# FPGA_BANKS.net
KiCad netlist of a schematic drawn in Altium Designer
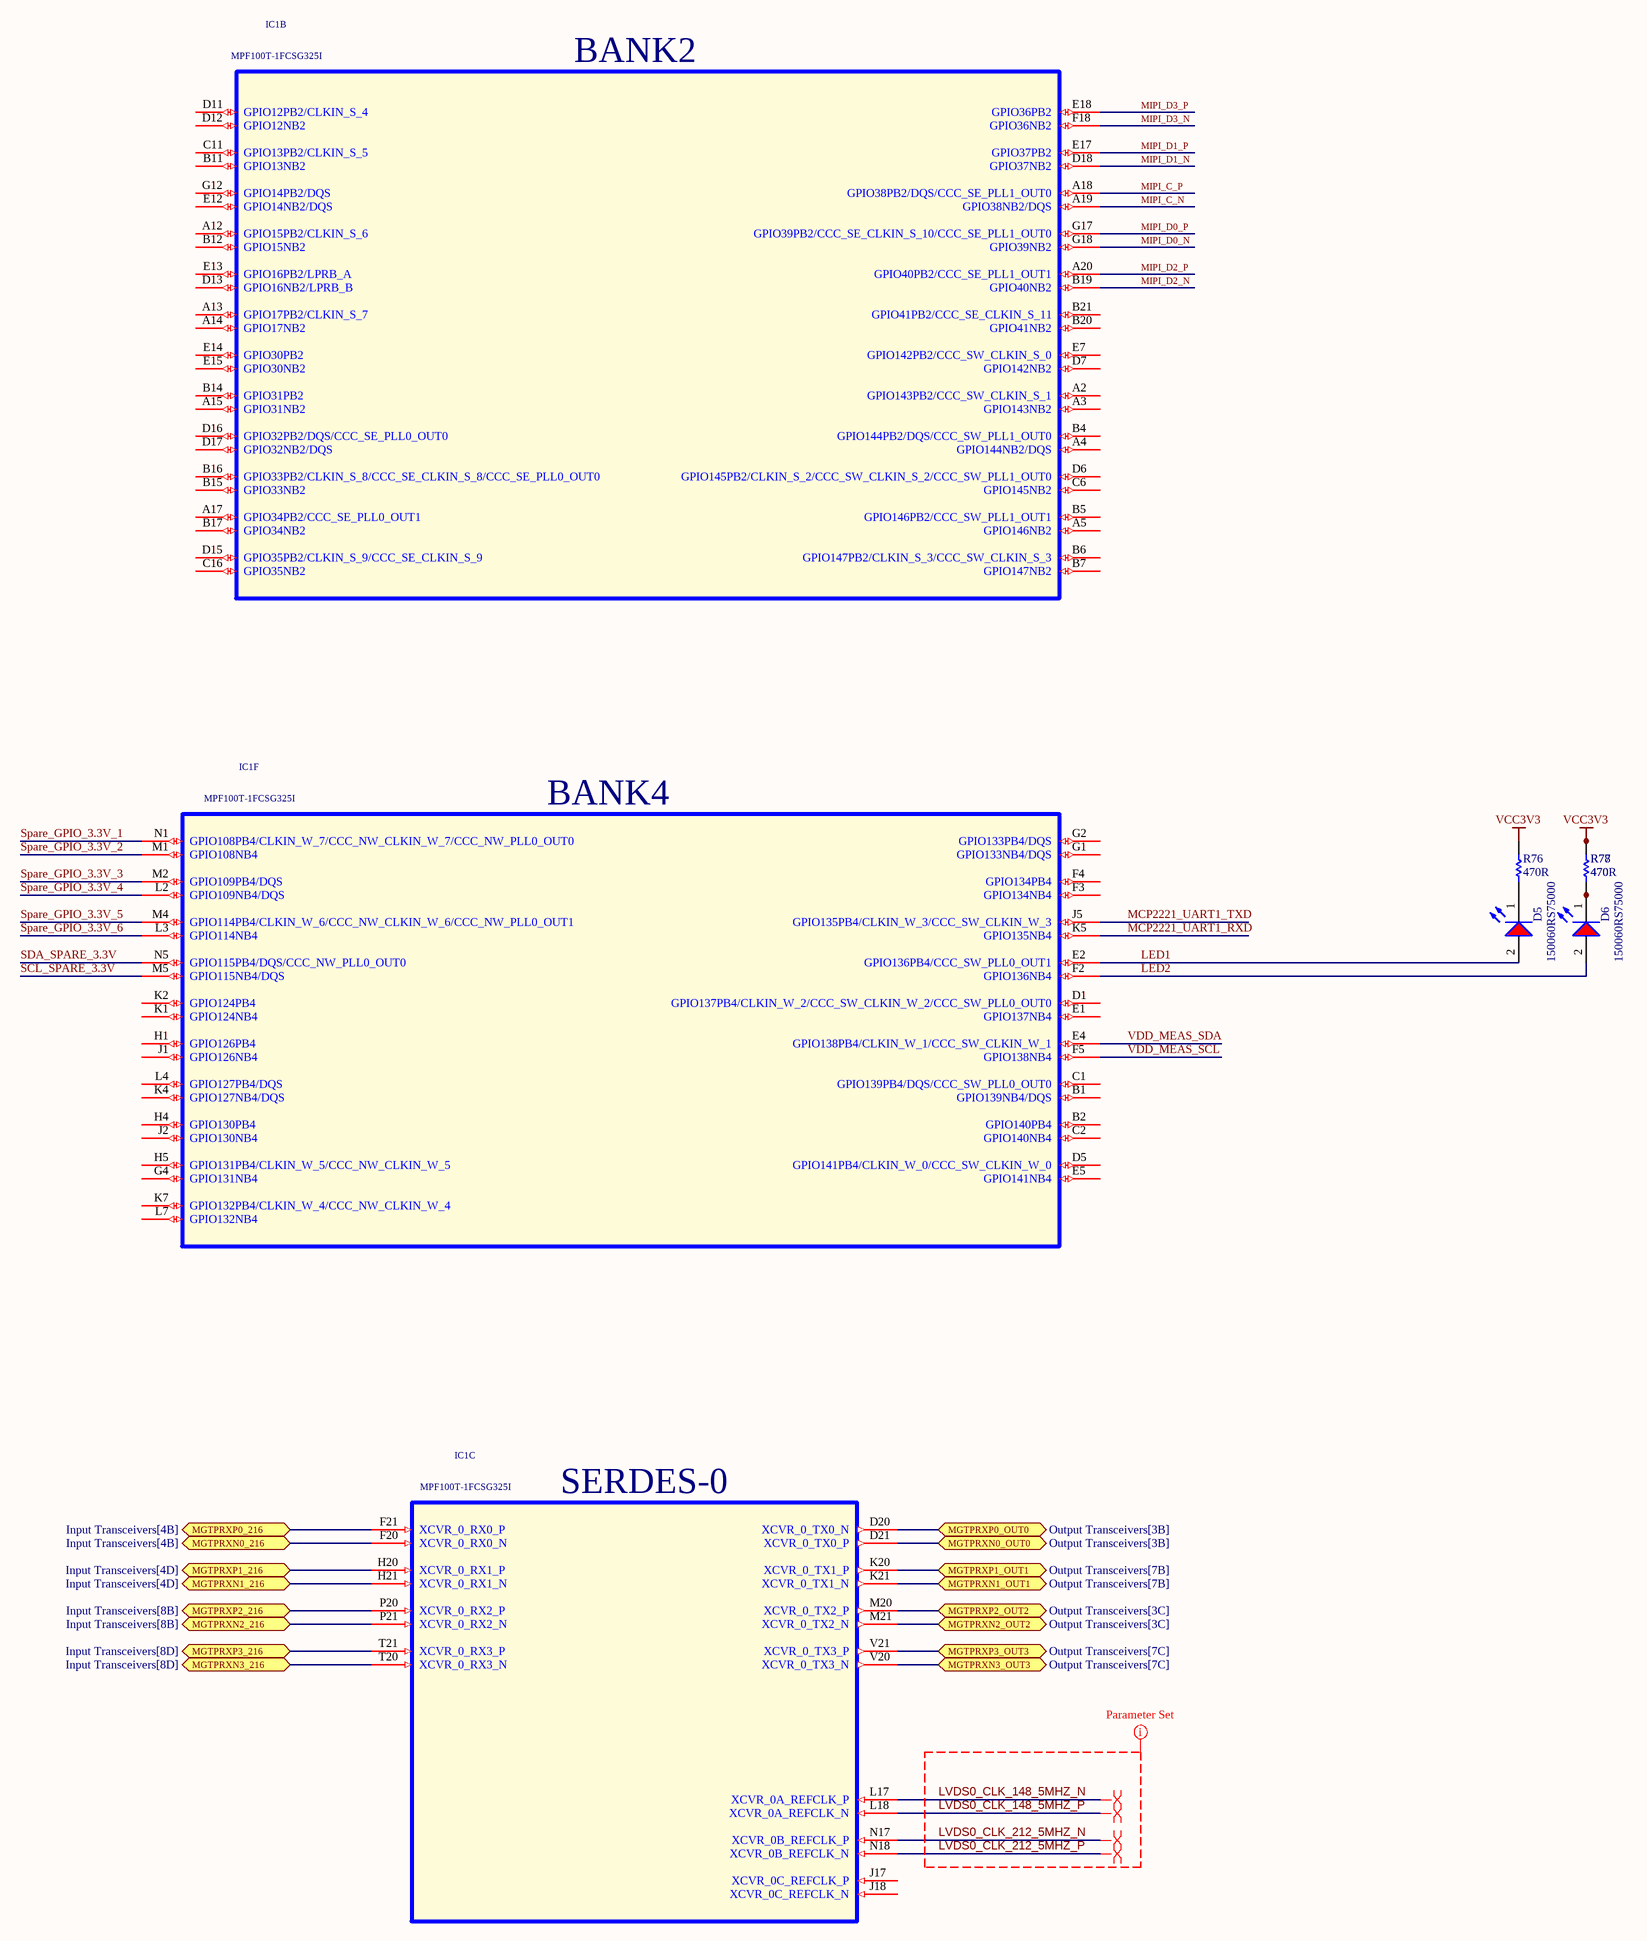
[diagram p0: FPGA_BANKS.SchDoc]

(export (version "E")
  (design (tool "Eeschema 10.0.6"))
  (components
    (comp (ref "D5")
      (value "150060RS75000")
      (footprint "WL-SMCW_0603_150060xx75000")
      (description "LED Low-Power Uni-Color Red 630nm 2V 2-Pin Chip 0603(1608Metric) T/R")
      (libsource (lib "Altium Content Vault") (part "LED_Red_2A-1K"))
    )
    (comp (ref "D6")
      (value "150060RS75000")
      (footprint "WL-SMCW_0603_150060xx75000")
      (description "LED Low-Power Uni-Color Red 630nm 2V 2-Pin Chip 0603(1608Metric) T/R")
      (libsource (lib "Altium Content Vault") (part "LED_Red_2A-1K"))
    )
    (comp (ref "IC1")
      (value "MPF100T-1FCSG325I")
      (footprint "PCB_Display_Doru:MPF100T-1FCSG325I")
      (fields (field (name "PART_NUMBER") "J00001"))
      (libsource (lib "PCB_Display_Doru") (part "MPF100T-1FCSG325I"))
    )
    (comp (ref "R76")
      (value "470R")
      (footprint "RESC1005X40X25ML05T10")
      (fields (field (name "PART NUMBER") "RC0402FR-07470RL") (field (name "MANUFACTURER") "Yageo / Phycomp"))
      (libsource (lib "Altium Content Vault") (part "RES"))
    )
    (comp (ref "R77")
      (value "470")
      (footprint "RESC1005X40X25ML05T10")
      (fields (field (name "PART NUMBER") "RC0402FR-07470RL") (field (name "MANUFACTURER") "Yageo / Phycomp"))
      (libsource (lib "Altium Content Vault") (part "RES"))
    )
    (comp (ref "R78")
      (value "470R")
      (footprint "RESC1005X40X25ML05T10")
      (fields (field (name "PART NUMBER") "RC0402FR-07470RL") (field (name "MANUFACTURER") "Yageo / Phycomp"))
      (libsource (lib "Altium Content Vault") (part "RES"))
    )
  )
  (nets
    (net (code "1") (name "/LED1") (class "Default")
      (node (ref "D5") (pin "2") (pinfunction "A_2") (pintype "passive"))
      (node (ref "IC1") (pin "E2") (pinfunction "GPIO136PB4/CCC_SW_PLL0_OUT1_E2") (pintype "bidirectional"))
    )
    (net (code "2") (name "/LED2") (class "Default")
      (node (ref "D6") (pin "2") (pinfunction "A_2") (pintype "passive"))
      (node (ref "IC1") (pin "F2") (pinfunction "GPIO136NB4_F2") (pintype "bidirectional"))
    )
    (net (code "3") (name "/LVDS0_CLK_148_5MHZ_N") (class "Default")
      (node (ref "IC1") (pin "L17") (pinfunction "XCVR_0A_REFCLK_P_L17") (pintype "input"))
    )
    (net (code "4") (name "/LVDS0_CLK_148_5MHZ_P") (class "Default")
      (node (ref "IC1") (pin "L18") (pinfunction "XCVR_0A_REFCLK_N_L18") (pintype "input"))
    )
    (net (code "5") (name "/LVDS0_CLK_212_5MHZ_N") (class "Default")
      (node (ref "IC1") (pin "N17") (pinfunction "XCVR_0B_REFCLK_P_N17") (pintype "input"))
    )
    (net (code "6") (name "/LVDS0_CLK_212_5MHZ_P") (class "Default")
      (node (ref "IC1") (pin "N18") (pinfunction "XCVR_0B_REFCLK_N_N18") (pintype "input"))
    )
    (net (code "7") (name "/MCP2221_UART1_RXD") (class "Default")
      (node (ref "IC1") (pin "K5") (pinfunction "GPIO135NB4_K5") (pintype "bidirectional"))
    )
    (net (code "8") (name "/MCP2221_UART1_TXD") (class "Default")
      (node (ref "IC1") (pin "J5") (pinfunction "GPIO135PB4/CLKIN_W_3/CCC_SW_CLKIN_W_3_J5") (pintype "bidirectional"))
    )
    (net (code "9") (name "/MGTPRXN0_216") (class "Default")
      (node (ref "IC1") (pin "F20") (pinfunction "XCVR_0_RX0_N_F20") (pintype "input"))
    )
    (net (code "10") (name "/MGTPRXN0_OUT0") (class "Default")
      (node (ref "IC1") (pin "D21") (pinfunction "XCVR_0_TX0_P_D21") (pintype "output"))
    )
    (net (code "11") (name "/MGTPRXN1_216") (class "Default")
      (node (ref "IC1") (pin "H21") (pinfunction "XCVR_0_RX1_N_H21") (pintype "input"))
    )
    (net (code "12") (name "/MGTPRXN1_OUT1") (class "Default")
      (node (ref "IC1") (pin "K21") (pinfunction "XCVR_0_TX1_N_K21") (pintype "output"))
    )
    (net (code "13") (name "/MGTPRXN2_216") (class "Default")
      (node (ref "IC1") (pin "P21") (pinfunction "XCVR_0_RX2_N_P21") (pintype "input"))
    )
    (net (code "14") (name "/MGTPRXN2_OUT2") (class "Default")
      (node (ref "IC1") (pin "M21") (pinfunction "XCVR_0_TX2_N_M21") (pintype "output"))
    )
    (net (code "15") (name "/MGTPRXN3_216") (class "Default")
      (node (ref "IC1") (pin "T20") (pinfunction "XCVR_0_RX3_N_T20") (pintype "input"))
    )
    (net (code "16") (name "/MGTPRXN3_OUT3") (class "Default")
      (node (ref "IC1") (pin "V20") (pinfunction "XCVR_0_TX3_N_V20") (pintype "output"))
    )
    (net (code "17") (name "/MGTPRXP0_216") (class "Default")
      (node (ref "IC1") (pin "F21") (pinfunction "XCVR_0_RX0_P_F21") (pintype "input"))
    )
    (net (code "18") (name "/MGTPRXP0_OUT0") (class "Default")
      (node (ref "IC1") (pin "D20") (pinfunction "XCVR_0_TX0_N_D20") (pintype "output"))
    )
    (net (code "19") (name "/MGTPRXP1_216") (class "Default")
      (node (ref "IC1") (pin "H20") (pinfunction "XCVR_0_RX1_P_H20") (pintype "input"))
    )
    (net (code "20") (name "/MGTPRXP1_OUT1") (class "Default")
      (node (ref "IC1") (pin "K20") (pinfunction "XCVR_0_TX1_P_K20") (pintype "output"))
    )
    (net (code "21") (name "/MGTPRXP2_216") (class "Default")
      (node (ref "IC1") (pin "P20") (pinfunction "XCVR_0_RX2_P_P20") (pintype "input"))
    )
    (net (code "22") (name "/MGTPRXP2_OUT2") (class "Default")
      (node (ref "IC1") (pin "M20") (pinfunction "XCVR_0_TX2_P_M20") (pintype "output"))
    )
    (net (code "23") (name "/MGTPRXP3_216") (class "Default")
      (node (ref "IC1") (pin "T21") (pinfunction "XCVR_0_RX3_P_T21") (pintype "input"))
    )
    (net (code "24") (name "/MGTPRXP3_OUT3") (class "Default")
      (node (ref "IC1") (pin "V21") (pinfunction "XCVR_0_TX3_P_V21") (pintype "output"))
    )
    (net (code "25") (name "/MIPI_C_N") (class "Default")
      (node (ref "IC1") (pin "A19") (pinfunction "GPIO38NB2/DQS_A19") (pintype "bidirectional"))
    )
    (net (code "26") (name "/MIPI_C_P") (class "Default")
      (node (ref "IC1") (pin "A18") (pinfunction "GPIO38PB2/DQS/CCC_SE_PLL1_OUT0_A18") (pintype "bidirectional"))
    )
    (net (code "27") (name "/MIPI_D0_N") (class "Default")
      (node (ref "IC1") (pin "G18") (pinfunction "GPIO39NB2_G18") (pintype "bidirectional"))
    )
    (net (code "28") (name "/MIPI_D0_P") (class "Default")
      (node (ref "IC1") (pin "G17") (pinfunction "GPIO39PB2/CCC_SE_CLKIN_S_10/CCC_SE_PLL1_OUT0_G17") (pintype "bidirectional"))
    )
    (net (code "29") (name "/MIPI_D1_N") (class "Default")
      (node (ref "IC1") (pin "D18") (pinfunction "GPIO37NB2_D18") (pintype "bidirectional"))
    )
    (net (code "30") (name "/MIPI_D1_P") (class "Default")
      (node (ref "IC1") (pin "E17") (pinfunction "GPIO37PB2_E17") (pintype "bidirectional"))
    )
    (net (code "31") (name "/MIPI_D2_N") (class "Default")
      (node (ref "IC1") (pin "B19") (pinfunction "GPIO40NB2_B19") (pintype "bidirectional"))
    )
    (net (code "32") (name "/MIPI_D2_P") (class "Default")
      (node (ref "IC1") (pin "A20") (pinfunction "GPIO40PB2/CCC_SE_PLL1_OUT1_A20") (pintype "bidirectional"))
    )
    (net (code "33") (name "/MIPI_D3_N") (class "Default")
      (node (ref "IC1") (pin "F18") (pinfunction "GPIO36NB2_F18") (pintype "bidirectional"))
    )
    (net (code "34") (name "/MIPI_D3_P") (class "Default")
      (node (ref "IC1") (pin "E18") (pinfunction "GPIO36PB2_E18") (pintype "bidirectional"))
    )
    (net (code "35") (name "/SCL_SPARE_3.3V") (class "Default")
      (node (ref "IC1") (pin "M5") (pinfunction "GPIO115NB4/DQS_M5") (pintype "bidirectional"))
    )
    (net (code "36") (name "/SDA_SPARE_3.3V") (class "Default")
      (node (ref "IC1") (pin "N5") (pinfunction "GPIO115PB4/DQS/CCC_NW_PLL0_OUT0_N5") (pintype "bidirectional"))
    )
    (net (code "37") (name "/Spare_GPIO_3.3V_1") (class "Default")
      (node (ref "IC1") (pin "N1") (pinfunction "GPIO108PB4/CLKIN_W_7/CCC_NW_CLKIN_W_7/CCC_NW_PLL0_OUT0_N1") (pintype "bidirectional"))
    )
    (net (code "38") (name "/Spare_GPIO_3.3V_2") (class "Default")
      (node (ref "IC1") (pin "M1") (pinfunction "GPIO108NB4_M1") (pintype "bidirectional"))
    )
    (net (code "39") (name "/Spare_GPIO_3.3V_3") (class "Default")
      (node (ref "IC1") (pin "M2") (pinfunction "GPIO109PB4/DQS_M2") (pintype "bidirectional"))
    )
    (net (code "40") (name "/Spare_GPIO_3.3V_4") (class "Default")
      (node (ref "IC1") (pin "L2") (pinfunction "GPIO109NB4/DQS_L2") (pintype "bidirectional"))
    )
    (net (code "41") (name "/Spare_GPIO_3.3V_5") (class "Default")
      (node (ref "IC1") (pin "M4") (pinfunction "GPIO114PB4/CLKIN_W_6/CCC_NW_CLKIN_W_6/CCC_NW_PLL0_OUT1_M4") (pintype "bidirectional"))
    )
    (net (code "42") (name "/Spare_GPIO_3.3V_6") (class "Default")
      (node (ref "IC1") (pin "L3") (pinfunction "GPIO114NB4_L3") (pintype "bidirectional"))
    )
    (net (code "43") (name "/VDD_MEAS_SCL") (class "Default")
      (node (ref "IC1") (pin "F5") (pinfunction "GPIO138NB4_F5") (pintype "bidirectional"))
    )
    (net (code "44") (name "/VDD_MEAS_SDA") (class "Default")
      (node (ref "IC1") (pin "E4") (pinfunction "GPIO138PB4/CLKIN_W_1/CCC_SW_CLKIN_W_1_E4") (pintype "bidirectional"))
    )
    (net (code "45") (name "Net-(D5-K)") (class "Default")
      (node (ref "D5") (pin "1") (pinfunction "K_1") (pintype "passive"))
      (node (ref "R76") (pin "1") (pinfunction "1_1") (pintype "passive"))
    )
    (net (code "46") (name "Net-(D6-K)") (class "Default")
      (node (ref "D6") (pin "1") (pinfunction "K_1") (pintype "passive"))
      (node (ref "R77") (pin "1") (pinfunction "1_1") (pintype "passive"))
      (node (ref "R78") (pin "1") (pinfunction "1_1") (pintype "passive"))
    )
    (net (code "47") (name "VCC3V3") (class "Default")
      (node (ref "R76") (pin "2") (pinfunction "2_2") (pintype "passive"))
      (node (ref "R77") (pin "2") (pinfunction "2_2") (pintype "passive"))
      (node (ref "R78") (pin "2") (pinfunction "2_2") (pintype "passive"))
    )
    (net (code "48") (name "unconnected-(IC1B-GPIO12NB2-PadD12)") (class "Default")
      (node (ref "IC1") (pin "D12") (pinfunction "GPIO12NB2_D12") (pintype "bidirectional"))
    )
    (net (code "49") (name "unconnected-(IC1B-GPIO12PB2{slash}CLKIN_S_4-PadD11)") (class "Default")
      (node (ref "IC1") (pin "D11") (pinfunction "GPIO12PB2/CLKIN_S_4_D11") (pintype "bidirectional"))
    )
    (net (code "50") (name "unconnected-(IC1B-GPIO13NB2-PadB11)") (class "Default")
      (node (ref "IC1") (pin "B11") (pinfunction "GPIO13NB2_B11") (pintype "bidirectional"))
    )
    (net (code "51") (name "unconnected-(IC1B-GPIO13PB2{slash}CLKIN_S_5-PadC11)") (class "Default")
      (node (ref "IC1") (pin "C11") (pinfunction "GPIO13PB2/CLKIN_S_5_C11") (pintype "bidirectional"))
    )
    (net (code "52") (name "unconnected-(IC1B-GPIO14NB2{slash}DQS-PadE12)") (class "Default")
      (node (ref "IC1") (pin "E12") (pinfunction "GPIO14NB2/DQS_E12") (pintype "bidirectional"))
    )
    (net (code "53") (name "unconnected-(IC1B-GPIO14PB2{slash}DQS-PadG12)") (class "Default")
      (node (ref "IC1") (pin "G12") (pinfunction "GPIO14PB2/DQS_G12") (pintype "bidirectional"))
    )
    (net (code "54") (name "unconnected-(IC1B-GPIO15NB2-PadB12)") (class "Default")
      (node (ref "IC1") (pin "B12") (pinfunction "GPIO15NB2_B12") (pintype "bidirectional"))
    )
    (net (code "55") (name "unconnected-(IC1B-GPIO15PB2{slash}CLKIN_S_6-PadA12)") (class "Default")
      (node (ref "IC1") (pin "A12") (pinfunction "GPIO15PB2/CLKIN_S_6_A12") (pintype "bidirectional"))
    )
    (net (code "56") (name "unconnected-(IC1B-GPIO16NB2{slash}LPRB_B-PadD13)") (class "Default")
      (node (ref "IC1") (pin "D13") (pinfunction "GPIO16NB2/LPRB_B_D13") (pintype "bidirectional"))
    )
    (net (code "57") (name "unconnected-(IC1B-GPIO16PB2{slash}LPRB_A-PadE13)") (class "Default")
      (node (ref "IC1") (pin "E13") (pinfunction "GPIO16PB2/LPRB_A_E13") (pintype "bidirectional"))
    )
    (net (code "58") (name "unconnected-(IC1B-GPIO17NB2-PadA14)") (class "Default")
      (node (ref "IC1") (pin "A14") (pinfunction "GPIO17NB2_A14") (pintype "bidirectional"))
    )
    (net (code "59") (name "unconnected-(IC1B-GPIO17PB2{slash}CLKIN_S_7-PadA13)") (class "Default")
      (node (ref "IC1") (pin "A13") (pinfunction "GPIO17PB2/CLKIN_S_7_A13") (pintype "bidirectional"))
    )
    (net (code "60") (name "unconnected-(IC1B-GPIO30NB2-PadE15)") (class "Default")
      (node (ref "IC1") (pin "E15") (pinfunction "GPIO30NB2_E15") (pintype "bidirectional"))
    )
    (net (code "61") (name "unconnected-(IC1B-GPIO30PB2-PadE14)") (class "Default")
      (node (ref "IC1") (pin "E14") (pinfunction "GPIO30PB2_E14") (pintype "bidirectional"))
    )
    (net (code "62") (name "unconnected-(IC1B-GPIO31NB2-PadA15)") (class "Default")
      (node (ref "IC1") (pin "A15") (pinfunction "GPIO31NB2_A15") (pintype "bidirectional"))
    )
    (net (code "63") (name "unconnected-(IC1B-GPIO31PB2-PadB14)") (class "Default")
      (node (ref "IC1") (pin "B14") (pinfunction "GPIO31PB2_B14") (pintype "bidirectional"))
    )
    (net (code "64") (name "unconnected-(IC1B-GPIO32NB2{slash}DQS-PadD17)") (class "Default")
      (node (ref "IC1") (pin "D17") (pinfunction "GPIO32NB2/DQS_D17") (pintype "bidirectional"))
    )
    (net (code "65") (name "unconnected-(IC1B-GPIO32PB2{slash}DQS{slash}CCC_SE_PLL0_OUT0-PadD16)") (class "Default")
      (node (ref "IC1") (pin "D16") (pinfunction "GPIO32PB2/DQS/CCC_SE_PLL0_OUT0_D16") (pintype "bidirectional"))
    )
    (net (code "66") (name "unconnected-(IC1B-GPIO33NB2-PadB15)") (class "Default")
      (node (ref "IC1") (pin "B15") (pinfunction "GPIO33NB2_B15") (pintype "bidirectional"))
    )
    (net (code "67") (name "unconnected-(IC1B-GPIO33PB2{slash}CLKIN_S_8{slash}CCC_SE_CLKIN_S_8{slash}CCC_SE_PLL0_OUT0-PadB16)") (class "Default")
      (node (ref "IC1") (pin "B16") (pinfunction "GPIO33PB2/CLKIN_S_8/CCC_SE_CLKIN_S_8/CCC_SE_PLL0_OUT0_B16") (pintype "bidirectional"))
    )
    (net (code "68") (name "unconnected-(IC1B-GPIO34NB2-PadB17)") (class "Default")
      (node (ref "IC1") (pin "B17") (pinfunction "GPIO34NB2_B17") (pintype "bidirectional"))
    )
    (net (code "69") (name "unconnected-(IC1B-GPIO34PB2{slash}CCC_SE_PLL0_OUT1-PadA17)") (class "Default")
      (node (ref "IC1") (pin "A17") (pinfunction "GPIO34PB2/CCC_SE_PLL0_OUT1_A17") (pintype "bidirectional"))
    )
    (net (code "70") (name "unconnected-(IC1B-GPIO35NB2-PadC16)") (class "Default")
      (node (ref "IC1") (pin "C16") (pinfunction "GPIO35NB2_C16") (pintype "bidirectional"))
    )
    (net (code "71") (name "unconnected-(IC1B-GPIO35PB2{slash}CLKIN_S_9{slash}CCC_SE_CLKIN_S_9-PadD15)") (class "Default")
      (node (ref "IC1") (pin "D15") (pinfunction "GPIO35PB2/CLKIN_S_9/CCC_SE_CLKIN_S_9_D15") (pintype "bidirectional"))
    )
    (net (code "72") (name "unconnected-(IC1B-GPIO41NB2-PadB20)") (class "Default")
      (node (ref "IC1") (pin "B20") (pinfunction "GPIO41NB2_B20") (pintype "bidirectional"))
    )
    (net (code "73") (name "unconnected-(IC1B-GPIO41PB2{slash}CCC_SE_CLKIN_S_11-PadB21)") (class "Default")
      (node (ref "IC1") (pin "B21") (pinfunction "GPIO41PB2/CCC_SE_CLKIN_S_11_B21") (pintype "bidirectional"))
    )
    (net (code "74") (name "unconnected-(IC1B-GPIO142NB2-PadD7)") (class "Default")
      (node (ref "IC1") (pin "D7") (pinfunction "GPIO142NB2_D7") (pintype "bidirectional"))
    )
    (net (code "75") (name "unconnected-(IC1B-GPIO142PB2{slash}CCC_SW_CLKIN_S_0-PadE7)") (class "Default")
      (node (ref "IC1") (pin "E7") (pinfunction "GPIO142PB2/CCC_SW_CLKIN_S_0_E7") (pintype "bidirectional"))
    )
    (net (code "76") (name "unconnected-(IC1B-GPIO143NB2-PadA3)") (class "Default")
      (node (ref "IC1") (pin "A3") (pinfunction "GPIO143NB2_A3") (pintype "bidirectional"))
    )
    (net (code "77") (name "unconnected-(IC1B-GPIO143PB2{slash}CCC_SW_CLKIN_S_1-PadA2)") (class "Default")
      (node (ref "IC1") (pin "A2") (pinfunction "GPIO143PB2/CCC_SW_CLKIN_S_1_A2") (pintype "bidirectional"))
    )
    (net (code "78") (name "unconnected-(IC1B-GPIO144NB2{slash}DQS-PadA4)") (class "Default")
      (node (ref "IC1") (pin "A4") (pinfunction "GPIO144NB2/DQS_A4") (pintype "bidirectional"))
    )
    (net (code "79") (name "unconnected-(IC1B-GPIO144PB2{slash}DQS{slash}CCC_SW_PLL1_OUT0-PadB4)") (class "Default")
      (node (ref "IC1") (pin "B4") (pinfunction "GPIO144PB2/DQS/CCC_SW_PLL1_OUT0_B4") (pintype "bidirectional"))
    )
    (net (code "80") (name "unconnected-(IC1B-GPIO145NB2-PadC6)") (class "Default")
      (node (ref "IC1") (pin "C6") (pinfunction "GPIO145NB2_C6") (pintype "bidirectional"))
    )
    (net (code "81") (name "unconnected-(IC1B-GPIO145PB2{slash}CLKIN_S_2{slash}CCC_SW_CLKIN_S_2{slash}CCC_SW_PLL1_OUT0-PadD6)") (class "Default")
      (node (ref "IC1") (pin "D6") (pinfunction "GPIO145PB2/CLKIN_S_2/CCC_SW_CLKIN_S_2/CCC_SW_PLL1_OUT0_D6") (pintype "bidirectional"))
    )
    (net (code "82") (name "unconnected-(IC1B-GPIO146NB2-PadA5)") (class "Default")
      (node (ref "IC1") (pin "A5") (pinfunction "GPIO146NB2_A5") (pintype "bidirectional"))
    )
    (net (code "83") (name "unconnected-(IC1B-GPIO146PB2{slash}CCC_SW_PLL1_OUT1-PadB5)") (class "Default")
      (node (ref "IC1") (pin "B5") (pinfunction "GPIO146PB2/CCC_SW_PLL1_OUT1_B5") (pintype "bidirectional"))
    )
    (net (code "84") (name "unconnected-(IC1B-GPIO147NB2-PadB7)") (class "Default")
      (node (ref "IC1") (pin "B7") (pinfunction "GPIO147NB2_B7") (pintype "bidirectional"))
    )
    (net (code "85") (name "unconnected-(IC1B-GPIO147PB2{slash}CLKIN_S_3{slash}CCC_SW_CLKIN_S_3-PadB6)") (class "Default")
      (node (ref "IC1") (pin "B6") (pinfunction "GPIO147PB2/CLKIN_S_3/CCC_SW_CLKIN_S_3_B6") (pintype "bidirectional"))
    )
    (net (code "86") (name "unconnected-(IC1C-XCVR_0C_REFCLK_N-PadJ18)") (class "Default")
      (node (ref "IC1") (pin "J18") (pinfunction "XCVR_0C_REFCLK_N_J18") (pintype "input"))
    )
    (net (code "87") (name "unconnected-(IC1C-XCVR_0C_REFCLK_P-PadJ17)") (class "Default")
      (node (ref "IC1") (pin "J17") (pinfunction "XCVR_0C_REFCLK_P_J17") (pintype "input"))
    )
    (net (code "88") (name "unconnected-(IC1F-GPIO124NB4-PadK1)") (class "Default")
      (node (ref "IC1") (pin "K1") (pinfunction "GPIO124NB4_K1") (pintype "bidirectional"))
    )
    (net (code "89") (name "unconnected-(IC1F-GPIO124PB4-PadK2)") (class "Default")
      (node (ref "IC1") (pin "K2") (pinfunction "GPIO124PB4_K2") (pintype "bidirectional"))
    )
    (net (code "90") (name "unconnected-(IC1F-GPIO126NB4-PadJ1)") (class "Default")
      (node (ref "IC1") (pin "J1") (pinfunction "GPIO126NB4_J1") (pintype "bidirectional"))
    )
    (net (code "91") (name "unconnected-(IC1F-GPIO126PB4-PadH1)") (class "Default")
      (node (ref "IC1") (pin "H1") (pinfunction "GPIO126PB4_H1") (pintype "bidirectional"))
    )
    (net (code "92") (name "unconnected-(IC1F-GPIO127NB4{slash}DQS-PadK4)") (class "Default")
      (node (ref "IC1") (pin "K4") (pinfunction "GPIO127NB4/DQS_K4") (pintype "bidirectional"))
    )
    (net (code "93") (name "unconnected-(IC1F-GPIO127PB4{slash}DQS-PadL4)") (class "Default")
      (node (ref "IC1") (pin "L4") (pinfunction "GPIO127PB4/DQS_L4") (pintype "bidirectional"))
    )
    (net (code "94") (name "unconnected-(IC1F-GPIO130NB4-PadJ2)") (class "Default")
      (node (ref "IC1") (pin "J2") (pinfunction "GPIO130NB4_J2") (pintype "bidirectional"))
    )
    (net (code "95") (name "unconnected-(IC1F-GPIO130PB4-PadH4)") (class "Default")
      (node (ref "IC1") (pin "H4") (pinfunction "GPIO130PB4_H4") (pintype "bidirectional"))
    )
    (net (code "96") (name "unconnected-(IC1F-GPIO131NB4-PadG4)") (class "Default")
      (node (ref "IC1") (pin "G4") (pinfunction "GPIO131NB4_G4") (pintype "bidirectional"))
    )
    (net (code "97") (name "unconnected-(IC1F-GPIO131PB4{slash}CLKIN_W_5{slash}CCC_NW_CLKIN_W_5-PadH5)") (class "Default")
      (node (ref "IC1") (pin "H5") (pinfunction "GPIO131PB4/CLKIN_W_5/CCC_NW_CLKIN_W_5_H5") (pintype "bidirectional"))
    )
    (net (code "98") (name "unconnected-(IC1F-GPIO132NB4-PadL7)") (class "Default")
      (node (ref "IC1") (pin "L7") (pinfunction "GPIO132NB4_L7") (pintype "bidirectional"))
    )
    (net (code "99") (name "unconnected-(IC1F-GPIO132PB4{slash}CLKIN_W_4{slash}CCC_NW_CLKIN_W_4-PadK7)") (class "Default")
      (node (ref "IC1") (pin "K7") (pinfunction "GPIO132PB4/CLKIN_W_4/CCC_NW_CLKIN_W_4_K7") (pintype "bidirectional"))
    )
    (net (code "100") (name "unconnected-(IC1F-GPIO133NB4{slash}DQS-PadG1)") (class "Default")
      (node (ref "IC1") (pin "G1") (pinfunction "GPIO133NB4/DQS_G1") (pintype "bidirectional"))
    )
    (net (code "101") (name "unconnected-(IC1F-GPIO133PB4{slash}DQS-PadG2)") (class "Default")
      (node (ref "IC1") (pin "G2") (pinfunction "GPIO133PB4/DQS_G2") (pintype "bidirectional"))
    )
    (net (code "102") (name "unconnected-(IC1F-GPIO134NB4-PadF3)") (class "Default")
      (node (ref "IC1") (pin "F3") (pinfunction "GPIO134NB4_F3") (pintype "bidirectional"))
    )
    (net (code "103") (name "unconnected-(IC1F-GPIO134PB4-PadF4)") (class "Default")
      (node (ref "IC1") (pin "F4") (pinfunction "GPIO134PB4_F4") (pintype "bidirectional"))
    )
    (net (code "104") (name "unconnected-(IC1F-GPIO137NB4-PadE1)") (class "Default")
      (node (ref "IC1") (pin "E1") (pinfunction "GPIO137NB4_E1") (pintype "bidirectional"))
    )
    (net (code "105") (name "unconnected-(IC1F-GPIO137PB4{slash}CLKIN_W_2{slash}CCC_SW_CLKIN_W_2{slash}CCC_SW_PLL0_OUT0-PadD1)") (class "Default")
      (node (ref "IC1") (pin "D1") (pinfunction "GPIO137PB4/CLKIN_W_2/CCC_SW_CLKIN_W_2/CCC_SW_PLL0_OUT0_D1") (pintype "bidirectional"))
    )
    (net (code "106") (name "unconnected-(IC1F-GPIO139NB4{slash}DQS-PadB1)") (class "Default")
      (node (ref "IC1") (pin "B1") (pinfunction "GPIO139NB4/DQS_B1") (pintype "bidirectional"))
    )
    (net (code "107") (name "unconnected-(IC1F-GPIO139PB4{slash}DQS{slash}CCC_SW_PLL0_OUT0-PadC1)") (class "Default")
      (node (ref "IC1") (pin "C1") (pinfunction "GPIO139PB4/DQS/CCC_SW_PLL0_OUT0_C1") (pintype "bidirectional"))
    )
    (net (code "108") (name "unconnected-(IC1F-GPIO140NB4-PadC2)") (class "Default")
      (node (ref "IC1") (pin "C2") (pinfunction "GPIO140NB4_C2") (pintype "bidirectional"))
    )
    (net (code "109") (name "unconnected-(IC1F-GPIO140PB4-PadB2)") (class "Default")
      (node (ref "IC1") (pin "B2") (pinfunction "GPIO140PB4_B2") (pintype "bidirectional"))
    )
    (net (code "110") (name "unconnected-(IC1F-GPIO141NB4-PadE5)") (class "Default")
      (node (ref "IC1") (pin "E5") (pinfunction "GPIO141NB4_E5") (pintype "bidirectional"))
    )
    (net (code "111") (name "unconnected-(IC1F-GPIO141PB4{slash}CLKIN_W_0{slash}CCC_SW_CLKIN_W_0-PadD5)") (class "Default")
      (node (ref "IC1") (pin "D5") (pinfunction "GPIO141PB4/CLKIN_W_0/CCC_SW_CLKIN_W_0_D5") (pintype "bidirectional"))
    )
  )
)
